# FIN_COURSE.net
KiCad netlist of a schematic drawn in Altium Designer
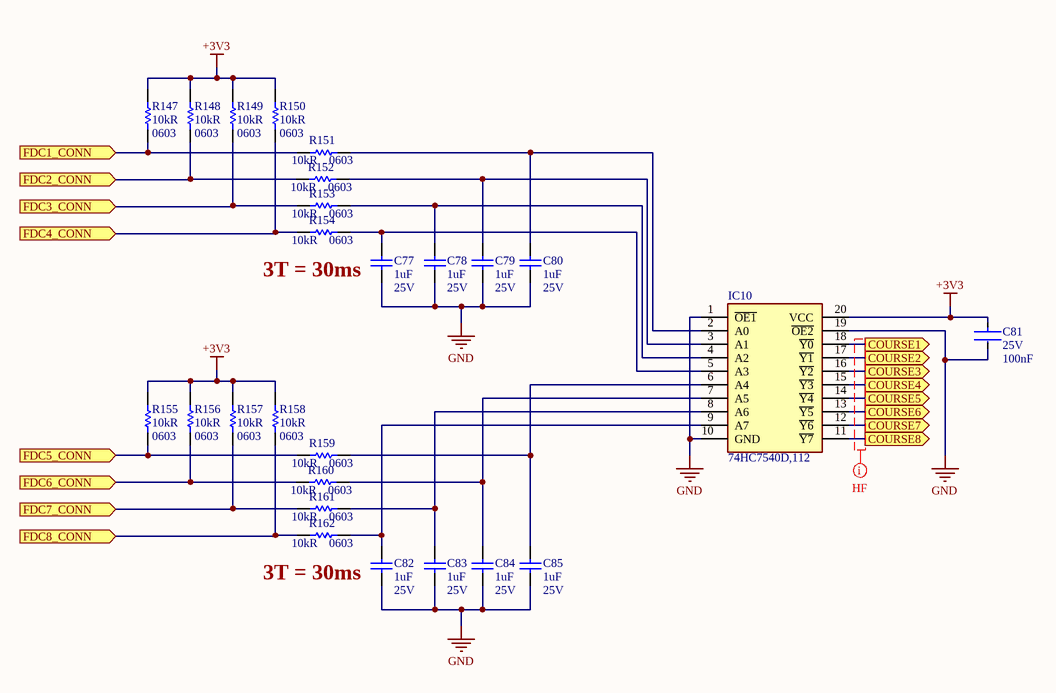
[diagram p0: FIN_COURSE.SchDoc]

(export (version "E")
  (design (tool "Eeschema 10.0.6"))
  (components
    (comp (ref "C77")
      (value "C0603C105K3PAC7867")
      (footprint "CAPC1608X90X35LL15T15")
      (fields
        (field (name "MANUFACTURER") "Kemet")
        (field (name "MANUFACTURER PART NUMBER") "C0603C105K3PACTU")
        (field (name "CAPACITANCE") "1uF")
        (field (name "TOLERANCE") "10%")
        (field (name "VOLTAGE RATING (DC)") "25V")
      )
      (libsource (lib "Altium Content Vault") (part "CAP"))
    )
    (comp (ref "C78")
      (value "C0603C105K3PAC7867")
      (footprint "CAPC1608X90X35LL15T15")
      (fields
        (field (name "MANUFACTURER") "Kemet")
        (field (name "MANUFACTURER PART NUMBER") "C0603C105K3PACTU")
        (field (name "CAPACITANCE") "1uF")
        (field (name "TOLERANCE") "10%")
        (field (name "VOLTAGE RATING (DC)") "25V")
      )
      (libsource (lib "Altium Content Vault") (part "CAP"))
    )
    (comp (ref "C79")
      (value "C0603C105K3PAC7867")
      (footprint "CAPC1608X90X35LL15T15")
      (fields
        (field (name "MANUFACTURER") "Kemet")
        (field (name "MANUFACTURER PART NUMBER") "C0603C105K3PACTU")
        (field (name "CAPACITANCE") "1uF")
        (field (name "TOLERANCE") "10%")
        (field (name "VOLTAGE RATING (DC)") "25V")
      )
      (libsource (lib "Altium Content Vault") (part "CAP"))
    )
    (comp (ref "C80")
      (value "C0603C105K3PAC7867")
      (footprint "CAPC1608X90X35LL15T15")
      (fields
        (field (name "MANUFACTURER") "Kemet")
        (field (name "MANUFACTURER PART NUMBER") "C0603C105K3PACTU")
        (field (name "CAPACITANCE") "1uF")
        (field (name "TOLERANCE") "10%")
        (field (name "VOLTAGE RATING (DC)") "25V")
      )
      (libsource (lib "Altium Content Vault") (part "CAP"))
    )
    (comp (ref "C81")
      (value "CGA3E2X7R1E104K080AA")
      (footprint "FP-CGA3E-0_3-0_1-MFG")
      (description "Cap Ceramic 100nF 25V X7R 10% Pad SMD 0603 +125°C Automotive T/R")
      (fields
        (field (name "VOLTAGE RATING (DC)") "25V")
        (field (name "CAPACITANCE") "100nF")
        (field (name "TOLERANCE") "10%")
        (field (name "MANUFACTURER") "TDK")
      )
      (libsource (lib "Altium Content Vault") (part "b4654b650e69147ec39a6b967a45e02"))
    )
    (comp (ref "C82")
      (value "C0603C105K3PAC7867")
      (footprint "CAPC1608X90X35LL15T15")
      (fields
        (field (name "MANUFACTURER") "Kemet")
        (field (name "MANUFACTURER PART NUMBER") "C0603C105K3PACTU")
        (field (name "CAPACITANCE") "1uF")
        (field (name "TOLERANCE") "10%")
        (field (name "VOLTAGE RATING (DC)") "25V")
      )
      (libsource (lib "Altium Content Vault") (part "CAP"))
    )
    (comp (ref "C83")
      (value "C0603C105K3PAC7867")
      (footprint "CAPC1608X90X35LL15T15")
      (fields
        (field (name "MANUFACTURER") "Kemet")
        (field (name "MANUFACTURER PART NUMBER") "C0603C105K3PACTU")
        (field (name "CAPACITANCE") "1uF")
        (field (name "TOLERANCE") "10%")
        (field (name "VOLTAGE RATING (DC)") "25V")
      )
      (libsource (lib "Altium Content Vault") (part "CAP"))
    )
    (comp (ref "C84")
      (value "C0603C105K3PAC7867")
      (footprint "CAPC1608X90X35LL15T15")
      (fields
        (field (name "MANUFACTURER") "Kemet")
        (field (name "MANUFACTURER PART NUMBER") "C0603C105K3PACTU")
        (field (name "CAPACITANCE") "1uF")
        (field (name "TOLERANCE") "10%")
        (field (name "VOLTAGE RATING (DC)") "25V")
      )
      (libsource (lib "Altium Content Vault") (part "CAP"))
    )
    (comp (ref "C85")
      (value "C0603C105K3PAC7867")
      (footprint "CAPC1608X90X35LL15T15")
      (fields
        (field (name "MANUFACTURER") "Kemet")
        (field (name "MANUFACTURER PART NUMBER") "C0603C105K3PACTU")
        (field (name "CAPACITANCE") "1uF")
        (field (name "TOLERANCE") "10%")
        (field (name "VOLTAGE RATING (DC)") "25V")
      )
      (libsource (lib "Altium Content Vault") (part "CAP"))
    )
    (comp (ref "IC10")
      (value "74HC7540D,112")
      (footprint "SamacSys:SOIC127P1032X265-20N")
      (description "Integrated Circuit")
      (fields (field (name "MOUSER PART NUMBER") "771-HC7540D112"))
      (libsource (lib "*") (part "74HC7540D,112"))
    )
    (comp (ref "R147")
      (value "ERJ3EKF1002V")
      (footprint "RESC1609X55X30LL15T15")
      (description "Chip Resistor, 10 KOhm, +/- 1%, 0.1 W, -55 to 155 degC, 0603 (1608 Metric), RoHS, Tape and Reel")
      (fields
        (field (name "RESISTANCE") "10kR")
        (field (name "CASE CODE (IMPERIAL)") "0603")
        (field (name "TOLERANCE") "1%")
        (field (name "MANUFACTURER") "Panasonic")
      )
      (libsource (lib "Altium Content Vault") (part "RES-2"))
    )
    (comp (ref "R148")
      (value "ERJ3EKF1002V")
      (footprint "RESC1609X55X30LL15T15")
      (description "Chip Resistor, 10 KOhm, +/- 1%, 0.1 W, -55 to 155 degC, 0603 (1608 Metric), RoHS, Tape and Reel")
      (fields
        (field (name "RESISTANCE") "10kR")
        (field (name "CASE CODE (IMPERIAL)") "0603")
        (field (name "TOLERANCE") "1%")
        (field (name "MANUFACTURER") "Panasonic")
      )
      (libsource (lib "Altium Content Vault") (part "RES-2"))
    )
    (comp (ref "R149")
      (value "ERJ3EKF1002V")
      (footprint "RESC1609X55X30LL15T15")
      (description "Chip Resistor, 10 KOhm, +/- 1%, 0.1 W, -55 to 155 degC, 0603 (1608 Metric), RoHS, Tape and Reel")
      (fields
        (field (name "RESISTANCE") "10kR")
        (field (name "CASE CODE (IMPERIAL)") "0603")
        (field (name "TOLERANCE") "1%")
        (field (name "MANUFACTURER") "Panasonic")
      )
      (libsource (lib "Altium Content Vault") (part "RES-2"))
    )
    (comp (ref "R150")
      (value "ERJ3EKF1002V")
      (footprint "RESC1609X55X30LL15T15")
      (description "Chip Resistor, 10 KOhm, +/- 1%, 0.1 W, -55 to 155 degC, 0603 (1608 Metric), RoHS, Tape and Reel")
      (fields
        (field (name "RESISTANCE") "10kR")
        (field (name "CASE CODE (IMPERIAL)") "0603")
        (field (name "TOLERANCE") "1%")
        (field (name "MANUFACTURER") "Panasonic")
      )
      (libsource (lib "Altium Content Vault") (part "RES-2"))
    )
    (comp (ref "R151")
      (value "ERJ3EKF1002V")
      (footprint "RESC1609X55X30LL15T15")
      (description "Chip Resistor, 10 KOhm, +/- 1%, 0.1 W, -55 to 155 degC, 0603 (1608 Metric), RoHS, Tape and Reel")
      (fields
        (field (name "RESISTANCE") "10kR")
        (field (name "CASE CODE (IMPERIAL)") "0603")
        (field (name "TOLERANCE") "1%")
        (field (name "MANUFACTURER") "Panasonic")
      )
      (libsource (lib "Altium Content Vault") (part "RES-2"))
    )
    (comp (ref "R152")
      (value "ERJ3EKF1002V")
      (footprint "RESC1609X55X30LL15T15")
      (description "Chip Resistor, 10 KOhm, +/- 1%, 0.1 W, -55 to 155 degC, 0603 (1608 Metric), RoHS, Tape and Reel")
      (fields
        (field (name "RESISTANCE") "10kR")
        (field (name "CASE CODE (IMPERIAL)") "0603")
        (field (name "TOLERANCE") "1%")
        (field (name "MANUFACTURER") "Panasonic")
      )
      (libsource (lib "Altium Content Vault") (part "RES-2"))
    )
    (comp (ref "R153")
      (value "ERJ3EKF1002V")
      (footprint "RESC1609X55X30LL15T15")
      (description "Chip Resistor, 10 KOhm, +/- 1%, 0.1 W, -55 to 155 degC, 0603 (1608 Metric), RoHS, Tape and Reel")
      (fields
        (field (name "RESISTANCE") "10kR")
        (field (name "CASE CODE (IMPERIAL)") "0603")
        (field (name "TOLERANCE") "1%")
        (field (name "MANUFACTURER") "Panasonic")
      )
      (libsource (lib "Altium Content Vault") (part "RES-2"))
    )
    (comp (ref "R154")
      (value "ERJ3EKF1002V")
      (footprint "RESC1609X55X30LL15T15")
      (description "Chip Resistor, 10 KOhm, +/- 1%, 0.1 W, -55 to 155 degC, 0603 (1608 Metric), RoHS, Tape and Reel")
      (fields
        (field (name "RESISTANCE") "10kR")
        (field (name "CASE CODE (IMPERIAL)") "0603")
        (field (name "TOLERANCE") "1%")
        (field (name "MANUFACTURER") "Panasonic")
      )
      (libsource (lib "Altium Content Vault") (part "RES-2"))
    )
    (comp (ref "R155")
      (value "ERJ3EKF1002V")
      (footprint "RESC1609X55X30LL15T15")
      (description "Chip Resistor, 10 KOhm, +/- 1%, 0.1 W, -55 to 155 degC, 0603 (1608 Metric), RoHS, Tape and Reel")
      (fields
        (field (name "RESISTANCE") "10kR")
        (field (name "CASE CODE (IMPERIAL)") "0603")
        (field (name "TOLERANCE") "1%")
        (field (name "MANUFACTURER") "Panasonic")
      )
      (libsource (lib "Altium Content Vault") (part "RES-2"))
    )
    (comp (ref "R156")
      (value "ERJ3EKF1002V")
      (footprint "RESC1609X55X30LL15T15")
      (description "Chip Resistor, 10 KOhm, +/- 1%, 0.1 W, -55 to 155 degC, 0603 (1608 Metric), RoHS, Tape and Reel")
      (fields
        (field (name "RESISTANCE") "10kR")
        (field (name "CASE CODE (IMPERIAL)") "0603")
        (field (name "TOLERANCE") "1%")
        (field (name "MANUFACTURER") "Panasonic")
      )
      (libsource (lib "Altium Content Vault") (part "RES-2"))
    )
    (comp (ref "R157")
      (value "ERJ3EKF1002V")
      (footprint "RESC1609X55X30LL15T15")
      (description "Chip Resistor, 10 KOhm, +/- 1%, 0.1 W, -55 to 155 degC, 0603 (1608 Metric), RoHS, Tape and Reel")
      (fields
        (field (name "RESISTANCE") "10kR")
        (field (name "CASE CODE (IMPERIAL)") "0603")
        (field (name "TOLERANCE") "1%")
        (field (name "MANUFACTURER") "Panasonic")
      )
      (libsource (lib "Altium Content Vault") (part "RES-2"))
    )
    (comp (ref "R158")
      (value "ERJ3EKF1002V")
      (footprint "RESC1609X55X30LL15T15")
      (description "Chip Resistor, 10 KOhm, +/- 1%, 0.1 W, -55 to 155 degC, 0603 (1608 Metric), RoHS, Tape and Reel")
      (fields
        (field (name "RESISTANCE") "10kR")
        (field (name "CASE CODE (IMPERIAL)") "0603")
        (field (name "TOLERANCE") "1%")
        (field (name "MANUFACTURER") "Panasonic")
      )
      (libsource (lib "Altium Content Vault") (part "RES-2"))
    )
    (comp (ref "R159")
      (value "ERJ3EKF1002V")
      (footprint "RESC1609X55X30LL15T15")
      (description "Chip Resistor, 10 KOhm, +/- 1%, 0.1 W, -55 to 155 degC, 0603 (1608 Metric), RoHS, Tape and Reel")
      (fields
        (field (name "RESISTANCE") "10kR")
        (field (name "CASE CODE (IMPERIAL)") "0603")
        (field (name "TOLERANCE") "1%")
        (field (name "MANUFACTURER") "Panasonic")
      )
      (libsource (lib "Altium Content Vault") (part "RES-2"))
    )
    (comp (ref "R160")
      (value "ERJ3EKF1002V")
      (footprint "RESC1609X55X30LL15T15")
      (description "Chip Resistor, 10 KOhm, +/- 1%, 0.1 W, -55 to 155 degC, 0603 (1608 Metric), RoHS, Tape and Reel")
      (fields
        (field (name "RESISTANCE") "10kR")
        (field (name "CASE CODE (IMPERIAL)") "0603")
        (field (name "TOLERANCE") "1%")
        (field (name "MANUFACTURER") "Panasonic")
      )
      (libsource (lib "Altium Content Vault") (part "RES-2"))
    )
    (comp (ref "R161")
      (value "ERJ3EKF1002V")
      (footprint "RESC1609X55X30LL15T15")
      (description "Chip Resistor, 10 KOhm, +/- 1%, 0.1 W, -55 to 155 degC, 0603 (1608 Metric), RoHS, Tape and Reel")
      (fields
        (field (name "RESISTANCE") "10kR")
        (field (name "CASE CODE (IMPERIAL)") "0603")
        (field (name "TOLERANCE") "1%")
        (field (name "MANUFACTURER") "Panasonic")
      )
      (libsource (lib "Altium Content Vault") (part "RES-2"))
    )
    (comp (ref "R162")
      (value "ERJ3EKF1002V")
      (footprint "RESC1609X55X30LL15T15")
      (description "Chip Resistor, 10 KOhm, +/- 1%, 0.1 W, -55 to 155 degC, 0603 (1608 Metric), RoHS, Tape and Reel")
      (fields
        (field (name "RESISTANCE") "10kR")
        (field (name "CASE CODE (IMPERIAL)") "0603")
        (field (name "TOLERANCE") "1%")
        (field (name "MANUFACTURER") "Panasonic")
      )
      (libsource (lib "Altium Content Vault") (part "RES-2"))
    )
  )
  (nets
    (net (code "1") (name "+3V3") (class "Default")
      (node (ref "C81") (pin "1") (pinfunction "1_1") (pintype "passive"))
      (node (ref "IC10") (pin "20") (pinfunction "VCC_20") (pintype "passive"))
      (node (ref "R147") (pin "2") (pinfunction "2_2") (pintype "passive"))
      (node (ref "R148") (pin "2") (pinfunction "2_2") (pintype "passive"))
      (node (ref "R149") (pin "2") (pinfunction "2_2") (pintype "passive"))
      (node (ref "R150") (pin "2") (pinfunction "2_2") (pintype "passive"))
      (node (ref "R155") (pin "2") (pinfunction "2_2") (pintype "passive"))
      (node (ref "R156") (pin "2") (pinfunction "2_2") (pintype "passive"))
      (node (ref "R157") (pin "2") (pinfunction "2_2") (pintype "passive"))
      (node (ref "R158") (pin "2") (pinfunction "2_2") (pintype "passive"))
    )
    (net (code "2") (name "/COURSE1") (class "Default")
      (node (ref "IC10") (pin "18") (pinfunction "~{Y0}_18") (pintype "passive"))
    )
    (net (code "3") (name "/COURSE2") (class "Default")
      (node (ref "IC10") (pin "17") (pinfunction "~{Y1}_17") (pintype "passive"))
    )
    (net (code "4") (name "/COURSE3") (class "Default")
      (node (ref "IC10") (pin "16") (pinfunction "~{Y2}_16") (pintype "passive"))
    )
    (net (code "5") (name "/COURSE4") (class "Default")
      (node (ref "IC10") (pin "15") (pinfunction "~{Y3}_15") (pintype "passive"))
    )
    (net (code "6") (name "/COURSE5") (class "Default")
      (node (ref "IC10") (pin "14") (pinfunction "~{Y4}_14") (pintype "passive"))
    )
    (net (code "7") (name "/COURSE6") (class "Default")
      (node (ref "IC10") (pin "13") (pinfunction "~{Y5}_13") (pintype "passive"))
    )
    (net (code "8") (name "/COURSE7") (class "Default")
      (node (ref "IC10") (pin "12") (pinfunction "~{Y6}_12") (pintype "passive"))
    )
    (net (code "9") (name "/COURSE8") (class "Default")
      (node (ref "IC10") (pin "11") (pinfunction "~{Y7}_11") (pintype "passive"))
    )
    (net (code "10") (name "/FDC1_CONN") (class "Default")
      (node (ref "R147") (pin "1") (pinfunction "1_1") (pintype "passive"))
      (node (ref "R151") (pin "2") (pinfunction "2_2") (pintype "passive"))
    )
    (net (code "11") (name "/FDC2_CONN") (class "Default")
      (node (ref "R148") (pin "1") (pinfunction "1_1") (pintype "passive"))
      (node (ref "R152") (pin "2") (pinfunction "2_2") (pintype "passive"))
    )
    (net (code "12") (name "/FDC3_CONN") (class "Default")
      (node (ref "R149") (pin "1") (pinfunction "1_1") (pintype "passive"))
      (node (ref "R153") (pin "2") (pinfunction "2_2") (pintype "passive"))
    )
    (net (code "13") (name "/FDC4_CONN") (class "Default")
      (node (ref "R150") (pin "1") (pinfunction "1_1") (pintype "passive"))
      (node (ref "R154") (pin "2") (pinfunction "2_2") (pintype "passive"))
    )
    (net (code "14") (name "/FDC5_CONN") (class "Default")
      (node (ref "R155") (pin "1") (pinfunction "1_1") (pintype "passive"))
      (node (ref "R159") (pin "2") (pinfunction "2_2") (pintype "passive"))
    )
    (net (code "15") (name "/FDC6_CONN") (class "Default")
      (node (ref "R156") (pin "1") (pinfunction "1_1") (pintype "passive"))
      (node (ref "R160") (pin "2") (pinfunction "2_2") (pintype "passive"))
    )
    (net (code "16") (name "/FDC7_CONN") (class "Default")
      (node (ref "R157") (pin "1") (pinfunction "1_1") (pintype "passive"))
      (node (ref "R161") (pin "2") (pinfunction "2_2") (pintype "passive"))
    )
    (net (code "17") (name "/FDC8_CONN") (class "Default")
      (node (ref "R158") (pin "1") (pinfunction "1_1") (pintype "passive"))
      (node (ref "R162") (pin "2") (pinfunction "2_2") (pintype "passive"))
    )
    (net (code "18") (name "GND") (class "Default")
      (node (ref "C77") (pin "1") (pinfunction "1_1") (pintype "passive"))
      (node (ref "C78") (pin "1") (pinfunction "1_1") (pintype "passive"))
      (node (ref "C79") (pin "1") (pinfunction "1_1") (pintype "passive"))
      (node (ref "C80") (pin "1") (pinfunction "1_1") (pintype "passive"))
      (node (ref "C81") (pin "2") (pinfunction "2_2") (pintype "passive"))
      (node (ref "C82") (pin "1") (pinfunction "1_1") (pintype "passive"))
      (node (ref "C83") (pin "1") (pinfunction "1_1") (pintype "passive"))
      (node (ref "C84") (pin "1") (pinfunction "1_1") (pintype "passive"))
      (node (ref "C85") (pin "1") (pinfunction "1_1") (pintype "passive"))
      (node (ref "IC10") (pin "1") (pinfunction "~{OE1}_1") (pintype "passive"))
      (node (ref "IC10") (pin "10") (pinfunction "GND_10") (pintype "passive"))
      (node (ref "IC10") (pin "19") (pinfunction "~{OE2}_19") (pintype "passive"))
    )
    (net (code "19") (name "Net-(IC10-A0)") (class "Default")
      (node (ref "C80") (pin "2") (pinfunction "2_2") (pintype "passive"))
      (node (ref "IC10") (pin "2") (pinfunction "A0_2") (pintype "passive"))
      (node (ref "R151") (pin "1") (pinfunction "1_1") (pintype "passive"))
    )
    (net (code "20") (name "Net-(IC10-A1)") (class "Default")
      (node (ref "C79") (pin "2") (pinfunction "2_2") (pintype "passive"))
      (node (ref "IC10") (pin "3") (pinfunction "A1_3") (pintype "passive"))
      (node (ref "R152") (pin "1") (pinfunction "1_1") (pintype "passive"))
    )
    (net (code "21") (name "Net-(IC10-A2)") (class "Default")
      (node (ref "C78") (pin "2") (pinfunction "2_2") (pintype "passive"))
      (node (ref "IC10") (pin "4") (pinfunction "A2_4") (pintype "passive"))
      (node (ref "R153") (pin "1") (pinfunction "1_1") (pintype "passive"))
    )
    (net (code "22") (name "Net-(IC10-A3)") (class "Default")
      (node (ref "C77") (pin "2") (pinfunction "2_2") (pintype "passive"))
      (node (ref "IC10") (pin "5") (pinfunction "A3_5") (pintype "passive"))
      (node (ref "R154") (pin "1") (pinfunction "1_1") (pintype "passive"))
    )
    (net (code "23") (name "Net-(IC10-A4)") (class "Default")
      (node (ref "C85") (pin "2") (pinfunction "2_2") (pintype "passive"))
      (node (ref "IC10") (pin "6") (pinfunction "A4_6") (pintype "passive"))
      (node (ref "R159") (pin "1") (pinfunction "1_1") (pintype "passive"))
    )
    (net (code "24") (name "Net-(IC10-A5)") (class "Default")
      (node (ref "C84") (pin "2") (pinfunction "2_2") (pintype "passive"))
      (node (ref "IC10") (pin "7") (pinfunction "A5_7") (pintype "passive"))
      (node (ref "R160") (pin "1") (pinfunction "1_1") (pintype "passive"))
    )
    (net (code "25") (name "Net-(IC10-A6)") (class "Default")
      (node (ref "C83") (pin "2") (pinfunction "2_2") (pintype "passive"))
      (node (ref "IC10") (pin "8") (pinfunction "A6_8") (pintype "passive"))
      (node (ref "R161") (pin "1") (pinfunction "1_1") (pintype "passive"))
    )
    (net (code "26") (name "Net-(IC10-A7)") (class "Default")
      (node (ref "C82") (pin "2") (pinfunction "2_2") (pintype "passive"))
      (node (ref "IC10") (pin "9") (pinfunction "A7_9") (pintype "passive"))
      (node (ref "R162") (pin "1") (pinfunction "1_1") (pintype "passive"))
    )
  )
)
